# Sheet1.net
KiCad netlist of a schematic drawn in Altium Designer
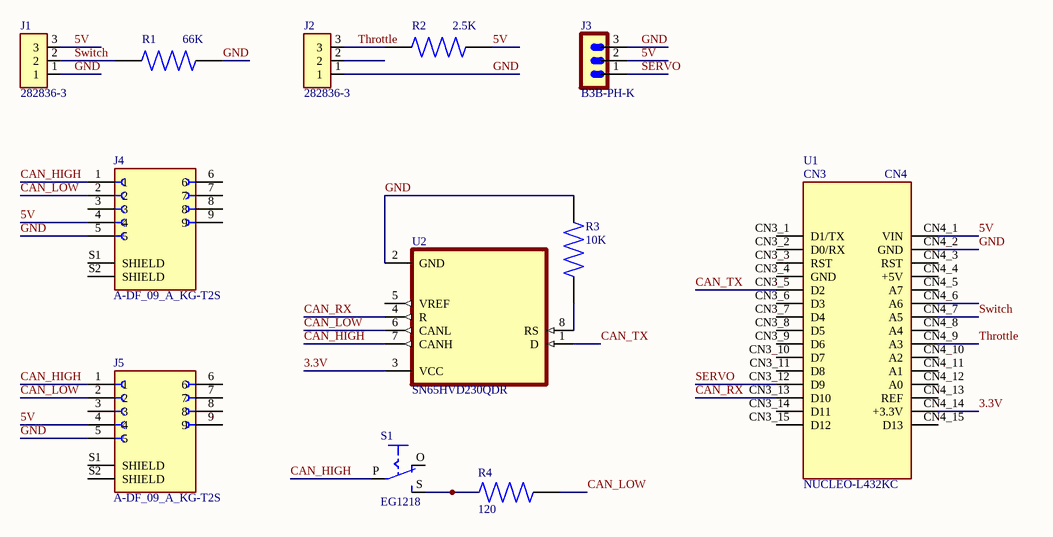
[diagram p0: Sheet1.SchDoc]

(export (version "E")
  (design (tool "Eeschema 10.0.6"))
  (components
    (comp (ref "J1")
      (value "282836-3")
      (footprint "TE_282836-3")
      (description "TERM BLOCK 3POS SIDE ENTRY 5MM")
      (libsource (lib "282836-3") (part "282836-3"))
    )
    (comp (ref "J2")
      (value "282836-3")
      (footprint "TE_282836-3")
      (description "TERM BLOCK 3POS SIDE ENTRY 5MM")
      (libsource (lib "282836-3") (part "282836-3"))
    )
    (comp (ref "J3")
      (value "B3B-PH-K")
      (footprint "B3B-PH-K")
      (description "Connector Header Through Hole 3 position 0.079 (2.00mm)")
      (fields (field (name "MF") "JST"))
      (libsource (lib "B3B-PH-K") (part "B3B-PH-K"))
    )
    (comp (ref "J4")
      (value "A-DF_09_A_KG-T2S")
      (footprint "ASSMANN_A-DF_09_A_KG-T2S")
      (description "9 Position D-Sub Receptacle, Female Sockets Connector")
      (fields (field (name "MF") "Assmann WSW") (field (name "MP") "A-DF 09 A/KG-T2S"))
      (libsource (lib "A-DF_09_A_KG-T2S") (part "A-DF_09_A_KG-T2S"))
    )
    (comp (ref "J5")
      (value "A-DF_09_A_KG-T2S")
      (footprint "ASSMANN_A-DF_09_A_KG-T2S")
      (description "9 Position D-Sub Receptacle, Female Sockets Connector")
      (fields (field (name "MF") "Assmann WSW") (field (name "MP") "A-DF 09 A/KG-T2S"))
      (libsource (lib "A-DF_09_A_KG-T2S") (part "A-DF_09_A_KG-T2S"))
    )
    (comp (ref "R1")
      (value "66K")
      (footprint "RESC3216X65N")
      (fields (field (name "MP") "KTR18EZPF9530"))
      (libsource (lib "KTR18EZPF9530") (part "KTR18EZPF9530"))
    )
    (comp (ref "R2")
      (value "2.5K")
      (footprint "RESC3216X65N")
      (fields (field (name "MP") "KTR18EZPF9530"))
      (libsource (lib "KTR18EZPF9530") (part "KTR18EZPF9530"))
    )
    (comp (ref "R3")
      (value "10K")
      (footprint "RESC3216X65N")
      (fields (field (name "MP") "KTR18EZPF9530"))
      (libsource (lib "KTR18EZPF9530") (part "KTR18EZPF9530"))
    )
    (comp (ref "R4")
      (value "120")
      (footprint "RESC3216X65N")
      (fields (field (name "MP") "KTR18EZPF9530"))
      (libsource (lib "KTR18EZPF9530") (part "KTR18EZPF9530"))
    )
    (comp (ref "S1") (value "EG1218") (footprint "EG1218:EG1218") (libsource (lib "EG1218") (part "EG1218")))
    (comp (ref "U1")
      (value "NUCLEO-L432KC")
      (footprint "MODULE_NUCLEO-L432KC")
      (description "STM32 Nucleo-32 development board with STM32L432KC MCU, supports Arduino connectivity")
      (libsource (lib "NUCLEO-L432KC") (part "NUCLEO-L432KC"))
    )
    (comp (ref "U2")
      (value "SN65HVD230QDR")
      (footprint "SOIC127P599X175-8N")
      (description "3.3-V CAN Transceiver with Standby Mode 8-SOIC -40 to 125")
      (fields (field (name "MF") "Texas Instruments"))
      (libsource (lib "SN65HVD230QDR") (part "SN65HVD230QDR"))
    )
  )
  (nets
    (net (code "1") (name "/3.3V") (class "Default")
      (node (ref "U1") (pin "CN4_14") (pinfunction "+3.3V_CN4_14") (pintype "power_in"))
      (node (ref "U2") (pin "3") (pinfunction "VCC_3") (pintype "power_in"))
    )
    (net (code "2") (name "/5V") (class "Default")
      (node (ref "J1") (pin "3") (pinfunction "3_3") (pintype "passive"))
      (node (ref "J3") (pin "2") (pinfunction "2_2") (pintype "passive"))
      (node (ref "J4") (pin "4") (pinfunction "4_4") (pintype "passive"))
      (node (ref "J5") (pin "4") (pinfunction "4_4") (pintype "passive"))
      (node (ref "R2") (pin "2") (pinfunction "2_2") (pintype "passive"))
      (node (ref "U1") (pin "CN4_1") (pinfunction "VIN_CN4_1") (pintype "power_in"))
    )
    (net (code "3") (name "/CAN_HIGH") (class "Default")
      (node (ref "J4") (pin "1") (pinfunction "1_1") (pintype "passive"))
      (node (ref "J5") (pin "1") (pinfunction "1_1") (pintype "passive"))
      (node (ref "S1") (pin "P") (pinfunction "P_P") (pintype "passive"))
      (node (ref "U2") (pin "7") (pinfunction "CANH_7") (pintype "output"))
    )
    (net (code "4") (name "/CAN_LOW") (class "Default")
      (node (ref "J4") (pin "2") (pinfunction "2_2") (pintype "passive"))
      (node (ref "J5") (pin "2") (pinfunction "2_2") (pintype "passive"))
      (node (ref "R4") (pin "2") (pinfunction "2_2") (pintype "passive"))
      (node (ref "U2") (pin "6") (pinfunction "CANL_6") (pintype "output"))
    )
    (net (code "5") (name "/CAN_RX") (class "Default")
      (node (ref "U1") (pin "CN3_13") (pinfunction "D10_CN3_13") (pintype "passive"))
      (node (ref "U2") (pin "4") (pinfunction "R_4") (pintype "output"))
    )
    (net (code "6") (name "/CAN_TX") (class "Default")
      (node (ref "U1") (pin "CN3_5") (pinfunction "D2_CN3_5") (pintype "power_in"))
      (node (ref "U2") (pin "1") (pinfunction "D_1") (pintype "input"))
    )
    (net (code "7") (name "/GND") (class "Default")
      (node (ref "J1") (pin "1") (pinfunction "1_1") (pintype "passive"))
      (node (ref "J2") (pin "1") (pinfunction "1_1") (pintype "passive"))
      (node (ref "J3") (pin "3") (pinfunction "3_3") (pintype "passive"))
      (node (ref "J4") (pin "5") (pinfunction "5_5") (pintype "passive"))
      (node (ref "J5") (pin "5") (pinfunction "5_5") (pintype "passive"))
      (node (ref "R1") (pin "2") (pinfunction "2_2") (pintype "passive"))
      (node (ref "R3") (pin "2") (pinfunction "2_2") (pintype "passive"))
      (node (ref "U1") (pin "CN4_2") (pinfunction "GND_CN4_2") (pintype "power_in"))
      (node (ref "U2") (pin "2") (pinfunction "GND_2") (pintype "power_in"))
    )
    (net (code "8") (name "/SERVO") (class "Default")
      (node (ref "J3") (pin "1") (pinfunction "1_1") (pintype "passive"))
      (node (ref "U1") (pin "CN3_12") (pinfunction "D9_CN3_12") (pintype "power_in"))
    )
    (net (code "9") (name "/Switch") (class "Default")
      (node (ref "J1") (pin "2") (pinfunction "2_2") (pintype "passive"))
      (node (ref "R1") (pin "1") (pinfunction "1_1") (pintype "passive"))
      (node (ref "U1") (pin "CN4_7") (pinfunction "A5_CN4_7") (pintype "passive"))
    )
    (net (code "10") (name "/Throttle") (class "Default")
      (node (ref "J2") (pin "3") (pinfunction "3_3") (pintype "passive"))
      (node (ref "R2") (pin "1") (pinfunction "1_1") (pintype "passive"))
      (node (ref "U1") (pin "CN4_9") (pinfunction "A3_CN4_9") (pintype "passive"))
    )
    (net (code "11") (name "Net-(R4-Pad1)") (class "Default")
      (node (ref "R4") (pin "1") (pinfunction "1_1") (pintype "passive"))
      (node (ref "S1") (pin "S") (pinfunction "S_S") (pintype "passive"))
    )
    (net (code "12") (name "Net-(U2-RS)") (class "Default")
      (node (ref "R3") (pin "1") (pinfunction "1_1") (pintype "passive"))
      (node (ref "U2") (pin "8") (pinfunction "RS_8") (pintype "input"))
    )
    (net (code "13") (name "unconnected-(J2-Pad2)") (class "Default")
      (node (ref "J2") (pin "2") (pinfunction "2_2") (pintype "passive"))
    )
    (net (code "14") (name "unconnected-(J4-Pad3)") (class "Default")
      (node (ref "J4") (pin "3") (pinfunction "3_3") (pintype "passive"))
    )
    (net (code "15") (name "unconnected-(J4-Pad6)") (class "Default")
      (node (ref "J4") (pin "6") (pinfunction "6_6") (pintype "passive"))
    )
    (net (code "16") (name "unconnected-(J4-Pad7)") (class "Default")
      (node (ref "J4") (pin "7") (pinfunction "7_7") (pintype "passive"))
    )
    (net (code "17") (name "unconnected-(J4-Pad8)") (class "Default")
      (node (ref "J4") (pin "8") (pinfunction "8_8") (pintype "passive"))
    )
    (net (code "18") (name "unconnected-(J4-Pad9)") (class "Default")
      (node (ref "J4") (pin "9") (pinfunction "9_9") (pintype "passive"))
    )
    (net (code "19") (name "unconnected-(J4-SHIELD-PadS1)") (class "Default")
      (node (ref "J4") (pin "S1") (pinfunction "SHIELD_S1") (pintype "passive"))
    )
    (net (code "20") (name "unconnected-(J4-SHIELD-PadS2)") (class "Default")
      (node (ref "J4") (pin "S2") (pinfunction "SHIELD_S2") (pintype "passive"))
    )
    (net (code "21") (name "unconnected-(J5-Pad3)") (class "Default")
      (node (ref "J5") (pin "3") (pinfunction "3_3") (pintype "passive"))
    )
    (net (code "22") (name "unconnected-(J5-Pad6)") (class "Default")
      (node (ref "J5") (pin "6") (pinfunction "6_6") (pintype "passive"))
    )
    (net (code "23") (name "unconnected-(J5-Pad7)") (class "Default")
      (node (ref "J5") (pin "7") (pinfunction "7_7") (pintype "passive"))
    )
    (net (code "24") (name "unconnected-(J5-Pad8)") (class "Default")
      (node (ref "J5") (pin "8") (pinfunction "8_8") (pintype "passive"))
    )
    (net (code "25") (name "unconnected-(J5-Pad9)") (class "Default")
      (node (ref "J5") (pin "9") (pinfunction "9_9") (pintype "passive"))
    )
    (net (code "26") (name "unconnected-(J5-SHIELD-PadS1)") (class "Default")
      (node (ref "J5") (pin "S1") (pinfunction "SHIELD_S1") (pintype "passive"))
    )
    (net (code "27") (name "unconnected-(J5-SHIELD-PadS2)") (class "Default")
      (node (ref "J5") (pin "S2") (pinfunction "SHIELD_S2") (pintype "passive"))
    )
    (net (code "28") (name "unconnected-(S1-PadO)") (class "Default")
      (node (ref "S1") (pin "O") (pinfunction "O_O") (pintype "passive"))
    )
    (net (code "29") (name "unconnected-(U1-+5V-PadCN4_4)") (class "Default")
      (node (ref "U1") (pin "CN4_4") (pinfunction "+5V_CN4_4") (pintype "power_in"))
    )
    (net (code "30") (name "unconnected-(U1-A0-PadCN4_12)") (class "Default")
      (node (ref "U1") (pin "CN4_12") (pinfunction "A0_CN4_12") (pintype "passive"))
    )
    (net (code "31") (name "unconnected-(U1-A1-PadCN4_11)") (class "Default")
      (node (ref "U1") (pin "CN4_11") (pinfunction "A1_CN4_11") (pintype "passive"))
    )
    (net (code "32") (name "unconnected-(U1-A2-PadCN4_10)") (class "Default")
      (node (ref "U1") (pin "CN4_10") (pinfunction "A2_CN4_10") (pintype "passive"))
    )
    (net (code "33") (name "unconnected-(U1-A4-PadCN4_8)") (class "Default")
      (node (ref "U1") (pin "CN4_8") (pinfunction "A4_CN4_8") (pintype "passive"))
    )
    (net (code "34") (name "unconnected-(U1-A6-PadCN4_6)") (class "Default")
      (node (ref "U1") (pin "CN4_6") (pinfunction "A6_CN4_6") (pintype "passive"))
    )
    (net (code "35") (name "unconnected-(U1-A7-PadCN4_5)") (class "Default")
      (node (ref "U1") (pin "CN4_5") (pinfunction "A7_CN4_5") (pintype "passive"))
    )
    (net (code "36") (name "unconnected-(U1-D0{slash}RX-PadCN3_2)") (class "Default")
      (node (ref "U1") (pin "CN3_2") (pinfunction "D0/RX_CN3_2") (pintype "power_in"))
    )
    (net (code "37") (name "unconnected-(U1-D1{slash}TX-PadCN3_1)") (class "Default")
      (node (ref "U1") (pin "CN3_1") (pinfunction "D1/TX_CN3_1") (pintype "power_in"))
    )
    (net (code "38") (name "unconnected-(U1-D3-PadCN3_6)") (class "Default")
      (node (ref "U1") (pin "CN3_6") (pinfunction "D3_CN3_6") (pintype "power_in"))
    )
    (net (code "39") (name "unconnected-(U1-D4-PadCN3_7)") (class "Default")
      (node (ref "U1") (pin "CN3_7") (pinfunction "D4_CN3_7") (pintype "power_in"))
    )
    (net (code "40") (name "unconnected-(U1-D5-PadCN3_8)") (class "Default")
      (node (ref "U1") (pin "CN3_8") (pinfunction "D5_CN3_8") (pintype "power_in"))
    )
    (net (code "41") (name "unconnected-(U1-D6-PadCN3_9)") (class "Default")
      (node (ref "U1") (pin "CN3_9") (pinfunction "D6_CN3_9") (pintype "power_in"))
    )
    (net (code "42") (name "unconnected-(U1-D7-PadCN3_10)") (class "Default")
      (node (ref "U1") (pin "CN3_10") (pinfunction "D7_CN3_10") (pintype "power_in"))
    )
    (net (code "43") (name "unconnected-(U1-D8-PadCN3_11)") (class "Default")
      (node (ref "U1") (pin "CN3_11") (pinfunction "D8_CN3_11") (pintype "power_in"))
    )
    (net (code "44") (name "unconnected-(U1-D11-PadCN3_14)") (class "Default")
      (node (ref "U1") (pin "CN3_14") (pinfunction "D11_CN3_14") (pintype "power_in"))
    )
    (net (code "45") (name "unconnected-(U1-D12-PadCN3_15)") (class "Default")
      (node (ref "U1") (pin "CN3_15") (pinfunction "D12_CN3_15") (pintype "power_in"))
    )
    (net (code "46") (name "unconnected-(U1-D13-PadCN4_15)") (class "Default")
      (node (ref "U1") (pin "CN4_15") (pinfunction "D13_CN4_15") (pintype "power_in"))
    )
    (net (code "47") (name "unconnected-(U1-GND-PadCN3_4)") (class "Default")
      (node (ref "U1") (pin "CN3_4") (pinfunction "GND_CN3_4") (pintype "power_in"))
    )
    (net (code "48") (name "unconnected-(U1-REF-PadCN4_13)") (class "Default")
      (node (ref "U1") (pin "CN4_13") (pinfunction "REF_CN4_13") (pintype "passive"))
    )
    (net (code "49") (name "unconnected-(U1-RST-PadCN3_3)") (class "Default")
      (node (ref "U1") (pin "CN3_3") (pinfunction "RST_CN3_3") (pintype "power_in"))
    )
    (net (code "50") (name "unconnected-(U1-RST-PadCN4_3)") (class "Default")
      (node (ref "U1") (pin "CN4_3") (pinfunction "RST_CN4_3") (pintype "passive"))
    )
    (net (code "51") (name "unconnected-(U2-VREF-Pad5)") (class "Default")
      (node (ref "U2") (pin "5") (pinfunction "VREF_5") (pintype "output"))
    )
  )
)
